# midi.net
KiCad netlist of a schematic drawn in Altium Designer
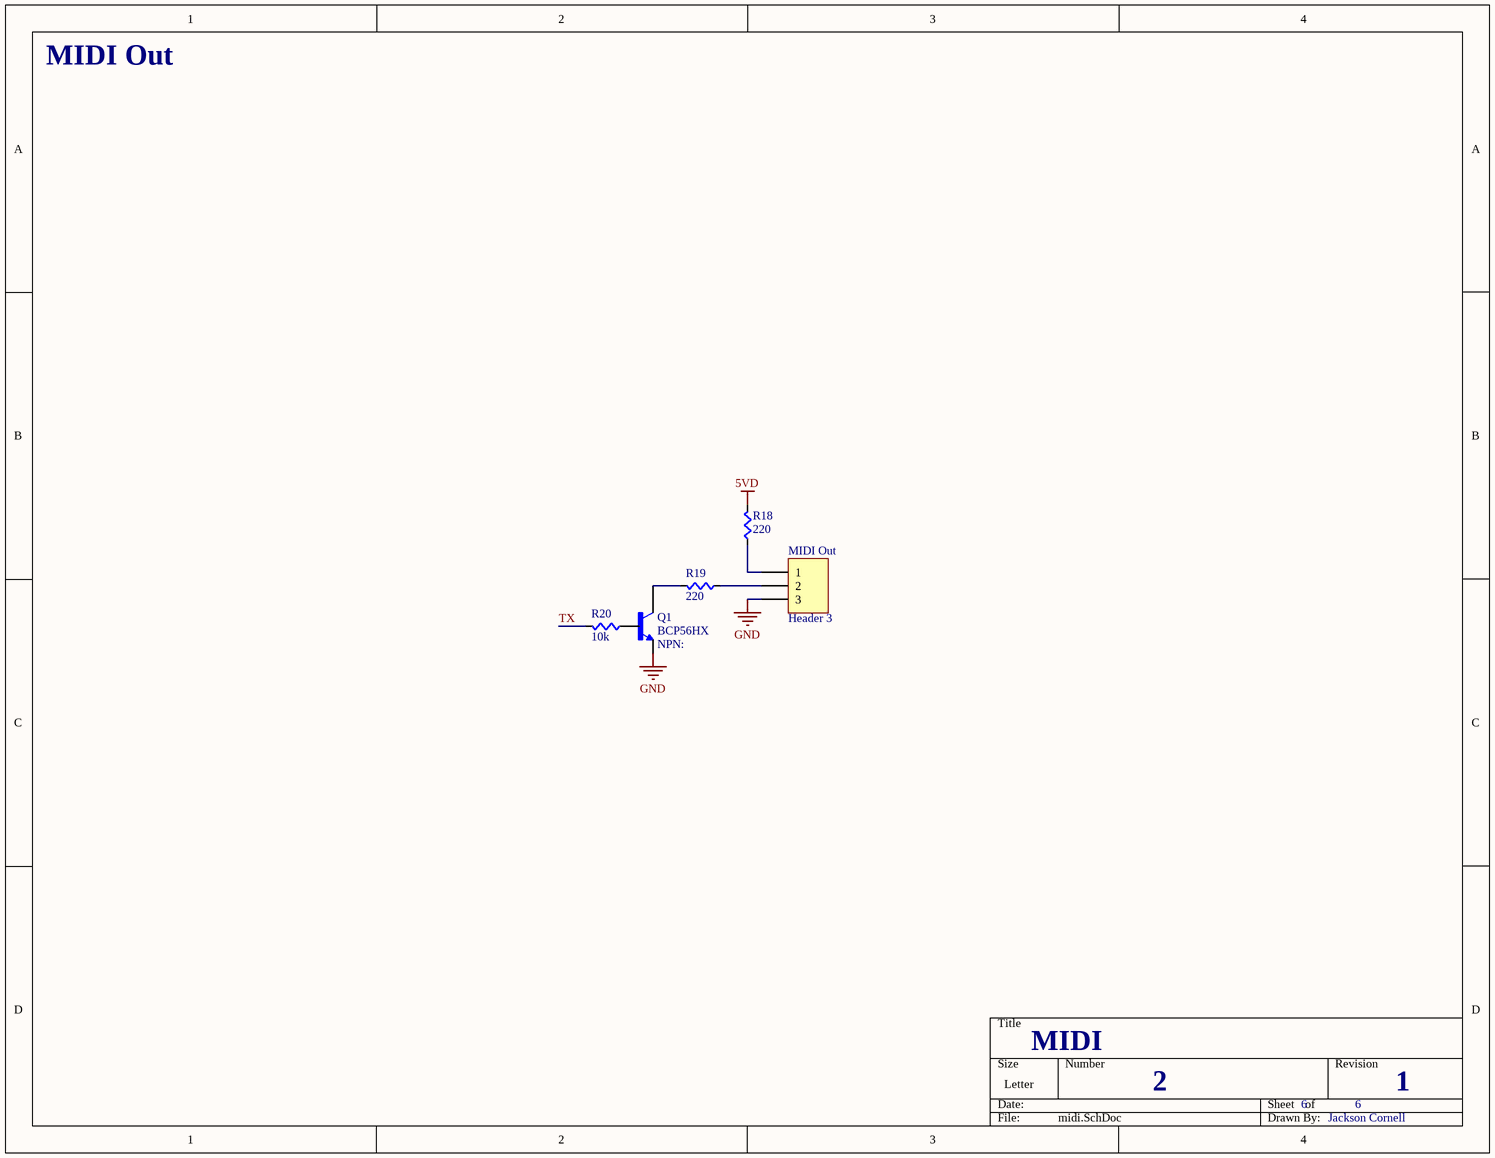
[diagram p0: midi.SchDoc]

(export (version "E")
  (design (tool "Eeschema 10.0.6"))
  (components
    (comp (ref "MIDI Out")
      (value "Header 3")
      (footprint "HDR1X3")
      (description "Header, 3-Pin")
      (fields (field (name "PUBLISHER") "Altium Limited"))
      (libsource (lib "Miscellaneous Connectors") (part "Header 3"))
    )
    (comp (ref "Q1")
      (value "BCP56HX")
      (footprint "SOT-223")
      (description "Bipolar (BJT) Transistor NPN 400V 1A 1.6W Surface Mount SOT-223")
      (fields (field (name "MP") "STN2580") (field (name "MF") "STMicroelectronics"))
      (libsource (lib "STN2580") (part "STN2580"))
    )
    (comp (ref "R18")
      (value "220")
      (footprint "RES0805")
      (fields (field (name "Comment") "Res"))
      (libsource (lib "Passives") (part "Res"))
    )
    (comp (ref "R19")
      (value "220")
      (footprint "RES0805")
      (fields (field (name "Comment") "Res"))
      (libsource (lib "Passives") (part "Res"))
    )
    (comp (ref "R20")
      (value "10k")
      (footprint "RES0805")
      (fields (field (name "Comment") "Res"))
      (libsource (lib "Passives") (part "Res"))
    )
  )
  (nets
    (net (code "1") (name "/TX") (class "Default")
      (node (ref "R20") (pin "1") (pinfunction "A_1") (pintype "passive"))
    )
    (net (code "2") (name "5VD") (class "Default")
      (node (ref "R18") (pin "1") (pinfunction "A_1") (pintype "passive"))
    )
    (net (code "3") (name "GND") (class "Default")
      (node (ref "MIDI Out") (pin "3") (pinfunction "3_3") (pintype "passive"))
      (node (ref "Q1") (pin "3") (pinfunction "E_3") (pintype "passive"))
    )
    (net (code "4") (name "Net-(Q1-B)") (class "Default")
      (node (ref "Q1") (pin "1") (pinfunction "B_1") (pintype "passive"))
      (node (ref "R20") (pin "2") (pinfunction "B_2") (pintype "passive"))
    )
    (net (code "5") (name "Net-(Q1-C2)") (class "Default")
      (node (ref "Q1") (pin "4") (pinfunction "C2_4") (pintype "passive"))
      (node (ref "R19") (pin "1") (pinfunction "A_1") (pintype "passive"))
    )
    (net (code "6") (name "Net-(R18-B)") (class "Default")
      (node (ref "MIDI Out") (pin "1") (pinfunction "1_1") (pintype "passive"))
      (node (ref "R18") (pin "2") (pinfunction "B_2") (pintype "passive"))
    )
    (net (code "7") (name "Net-(R19-B)") (class "Default")
      (node (ref "MIDI Out") (pin "2") (pinfunction "2_2") (pintype "passive"))
      (node (ref "R19") (pin "2") (pinfunction "B_2") (pintype "passive"))
    )
    (net (code "8") (name "unconnected-(Q1-C1-Pad2)") (class "Default")
      (node (ref "Q1") (pin "2") (pinfunction "C1_2") (pintype "passive"))
    )
  )
)
